# Spektrum_Adapter_SMD.net
KiCad netlist of a schematic drawn in Altium Designer
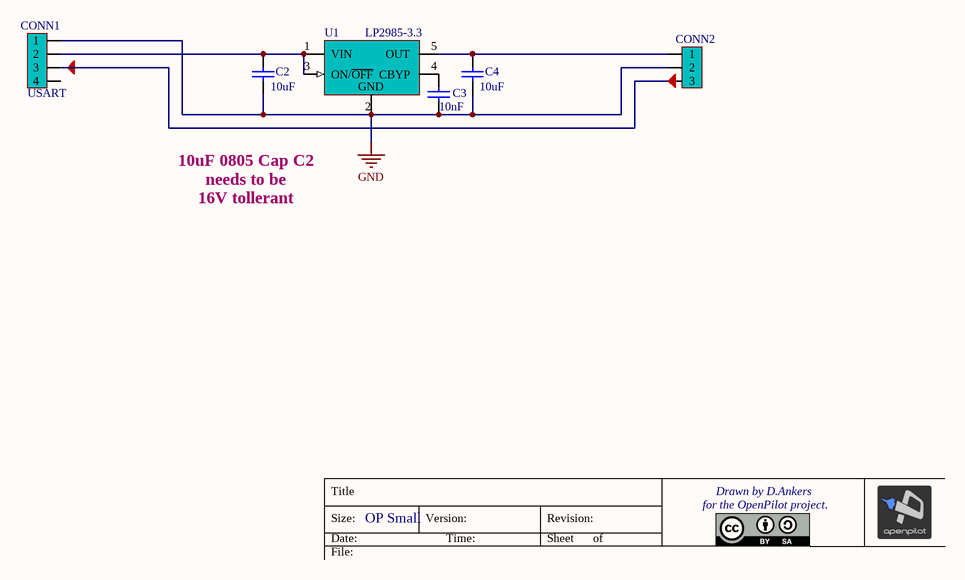
[diagram p0: Spektrum Adapter SMD.SchDoc]

(export (version "E")
  (design (tool "Eeschema 10.0.6"))
  (components
    (comp (ref "C2")
      (value "10uF")
      (footprint "CAP805L")
      (description "Capacitor SMD")
      (fields (field (name "Comment") "Cap805") (field (name "PUBLISHER") "The OpenPilot Project"))
      (libsource (lib "OpenPilot") (part "Cap805"))
    )
    (comp (ref "C3")
      (value "10nF")
      (footprint "CAP603L")
      (description "Capacitor SMD")
      (fields (field (name "Comment") "Cap603") (field (name "PUBLISHER") "The OpenPilot Project"))
      (libsource (lib "OpenPilot") (part "Cap603"))
    )
    (comp (ref "C4")
      (value "10uF")
      (footprint "CAP805L")
      (description "Capacitor SMD")
      (fields (field (name "Comment") "Cap805") (field (name "PUBLISHER") "The OpenPilot Project"))
      (libsource (lib "OpenPilot") (part "Cap805"))
    )
    (comp (ref "CONN1")
      (value "USART")
      (footprint "JST SH 4 Pin Side Entry")
      (description "JST-SH 4-pin Side Entry Socket")
      (fields (field (name "MANUFACTURER") "Generic Components"))
      (libsource (lib "OpenPilot") (part "JST-SH 4-pin Side Entry Socket"))
    )
    (comp (ref "CONN2")
      (value "JST ZH 3 Pin")
      (footprint "JST ZH SMD 3 PIN SIDE ENTRY")
      (description "JST ZH 1.5mm 3-pin Side Entry Socket")
      (fields
        (field (name "MANUFACTURER") "Generic Components")
        (field (name "PUBLISHER") "The OpenPilot Project")
      )
      (libsource (lib "OpenPilot") (part "JST ZH 3-pin Side Entry Socket"))
    )
    (comp (ref "U1")
      (value "LP2985-3.3")
      (footprint "SOT23-5L")
      (description "3.3V 150mA LDO Regulator")
      (libsource (lib "OpenPilot") (part "LP2985-3.3"))
    )
  )
  (nets
    (net (code "1") (name "GND") (class "Default")
      (node (ref "C2") (pin "2") (pinfunction "2_2") (pintype "passive"))
      (node (ref "C3") (pin "2") (pinfunction "2_2") (pintype "passive"))
      (node (ref "C4") (pin "2") (pinfunction "2_2") (pintype "passive"))
      (node (ref "CONN1") (pin "1") (pinfunction "1_1") (pintype "passive"))
      (node (ref "CONN2") (pin "2") (pinfunction "2_2") (pintype "power_in"))
      (node (ref "U1") (pin "2") (pinfunction "GND_2") (pintype "power_in"))
    )
    (net (code "2") (name "Net-(CONN1-Pad3)") (class "Default")
      (node (ref "CONN1") (pin "3") (pinfunction "3_3") (pintype "passive"))
      (node (ref "CONN2") (pin "3") (pinfunction "3_3") (pintype "passive"))
    )
    (net (code "3") (name "Net-(U1-CBYP)") (class "Default")
      (node (ref "C3") (pin "1") (pinfunction "1_1") (pintype "passive"))
      (node (ref "U1") (pin "4") (pinfunction "CBYP_4") (pintype "passive"))
    )
    (net (code "4") (name "Net-(U1-ON{slash}~{OFF})") (class "Default")
      (node (ref "C2") (pin "1") (pinfunction "1_1") (pintype "passive"))
      (node (ref "CONN1") (pin "2") (pinfunction "2_2") (pintype "passive"))
      (node (ref "U1") (pin "1") (pinfunction "VIN_1") (pintype "power_in"))
      (node (ref "U1") (pin "3") (pinfunction "ON/~{OFF}_3") (pintype "input"))
    )
    (net (code "5") (name "Net-(U1-OUT)") (class "Default")
      (node (ref "C4") (pin "1") (pinfunction "1_1") (pintype "passive"))
      (node (ref "CONN2") (pin "1") (pinfunction "1_1") (pintype "power_in"))
      (node (ref "U1") (pin "5") (pinfunction "OUT_5") (pintype "power_in"))
    )
    (net (code "6") (name "unconnected-(CONN1-Pad4)") (class "Default")
      (node (ref "CONN1") (pin "4") (pinfunction "4_4") (pintype "passive"))
    )
  )
)
